# SIM800C.net
KiCad netlist of a schematic drawn in Altium Designer
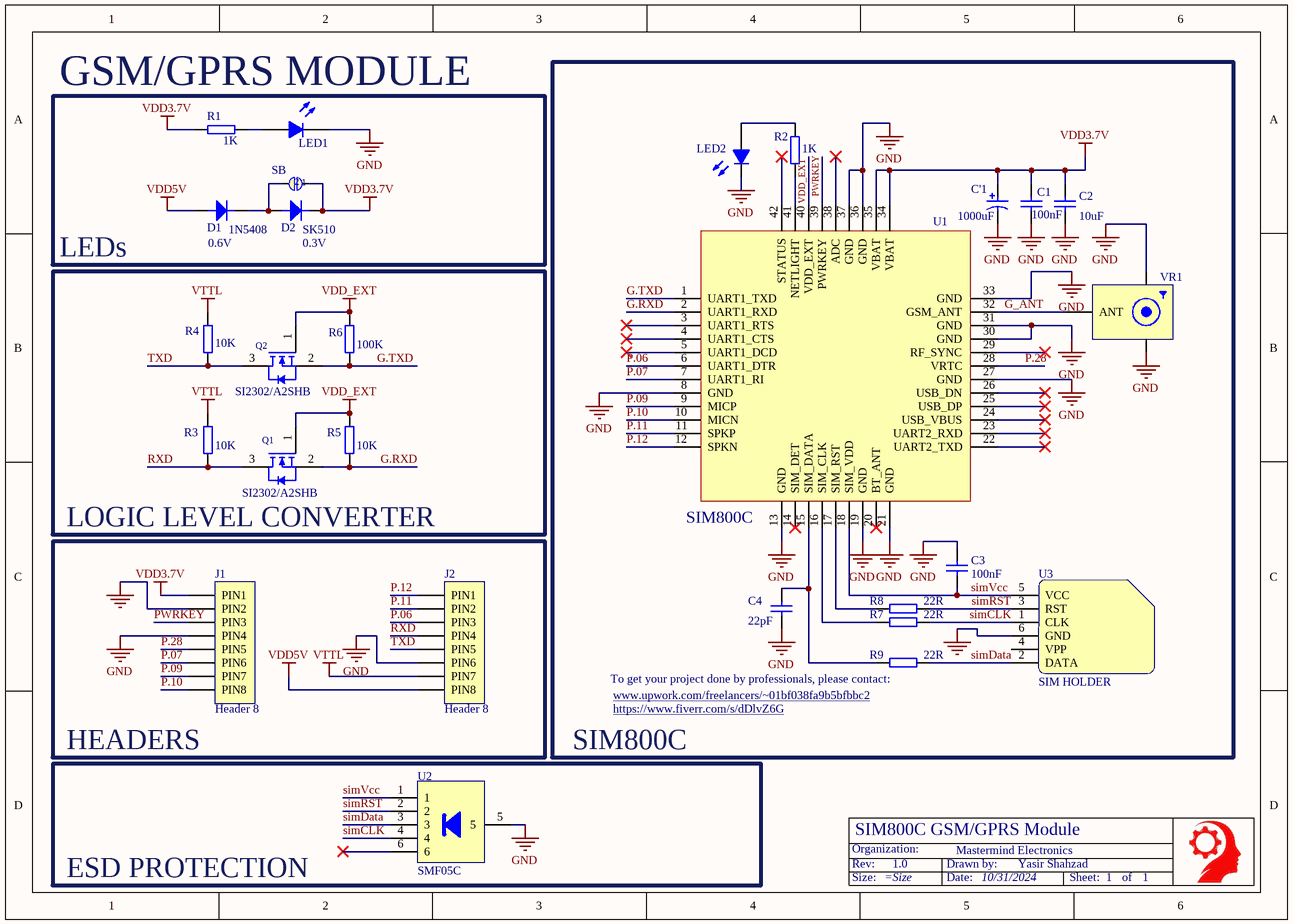
[diagram p0: SIM800C.SchDoc]

(export (version "E")
  (design (tool "Eeschema 10.0.6"))
  (components
    (comp (ref "*")
      (value "TitleBlock")
      (description "Title Block for Schematic Sheets")
      (libsource (lib "mastermind") (part "TitleBlock"))
    )
    (comp (ref "C'1") (value "1000uF") (footprint "D") (libsource (lib "SIM800C") (part "Taltium")))
    (comp (ref "C1")
      (value "10%")
      (footprint "0603C")
      (description "Chip capacitor")
      (libsource (lib "SIM800C") (part "CAP0603_NPOL"))
    )
    (comp (ref "C2")
      (value "10%")
      (footprint "0603C")
      (description "Chip capacitor")
      (libsource (lib "SIM800C") (part "CAP0603_NPOL"))
    )
    (comp (ref "C3")
      (value "10%")
      (footprint "0603C")
      (description "Chip capacitor")
      (libsource (lib "SIM800C") (part "CAP0603_NPOL"))
    )
    (comp (ref "C4")
      (value "10%")
      (footprint "0603C")
      (description "Chip capacitor")
      (libsource (lib "SIM800C") (part "CAP0603_NPOL"))
    )
    (comp (ref "D1")
      (value "DIODE-DO214-AC")
      (footprint "SOD123")
      (libsource (lib "SIM800C") (part "DIODE-DO214-AC"))
    )
    (comp (ref "D2")
      (value "DIODE-DO214-AC")
      (footprint "SOD123")
      (libsource (lib "SIM800C") (part "DIODE-DO214-AC"))
    )
    (comp (ref "J1")
      (value "Header 8")
      (footprint "HDR1X8")
      (description "Header, 8-Pin")
      (fields (field (name "PUBLISHER") "Altium Limited"))
      (libsource (lib "SIM800C") (part "Header 8"))
    )
    (comp (ref "J2")
      (value "Header 8")
      (footprint "HDR1X8")
      (description "Header, 8-Pin")
      (fields (field (name "PUBLISHER") "Altium Limited"))
      (libsource (lib "SIM800C") (part "Header 8"))
    )
    (comp (ref "LED1")
      (value "LED")
      (footprint "0603LED")
      (description "SMD lamp beads")
      (libsource (lib "SIM800C") (part "LEDCHIP-LED0603"))
    )
    (comp (ref "LED2")
      (value "LED")
      (footprint "0603LED")
      (description "SMD lamp beads")
      (libsource (lib "SIM800C") (part "LEDCHIP-LED0603"))
    )
    (comp (ref "Q1")
      (value "A2SHB")
      (footprint "SOT23")
      (description "N Channel Mosfet")
      (libsource (lib "adafruit") (part "BSS138"))
    )
    (comp (ref "Q2")
      (value "A2SHB")
      (footprint "SOT23")
      (description "N Channel Mosfet")
      (libsource (lib "adafruit") (part "BSS138"))
    )
    (comp (ref "R1")
      (value "5%")
      (footprint "0603")
      (description "Chip Resistor")
      (libsource (lib "") (part "RESISTOR_1"))
    )
    (comp (ref "R2")
      (value "5%")
      (footprint "0603")
      (description "Chip Resistor")
      (libsource (lib "") (part "RESISTOR_2"))
    )
    (comp (ref "R3")
      (value "5%")
      (footprint "0603")
      (description "Chip Resistor")
      (libsource (lib "SIM800C") (part "RESISTOR"))
    )
    (comp (ref "R4")
      (value "5%")
      (footprint "0603")
      (description "Chip Resistor")
      (libsource (lib "") (part "RESISTOR_1"))
    )
    (comp (ref "R5")
      (value "5%")
      (footprint "0603")
      (description "Chip Resistor")
      (libsource (lib "") (part "RESISTOR_1"))
    )
    (comp (ref "R6")
      (value "5%")
      (footprint "0603")
      (description "Chip Resistor")
      (libsource (lib "") (part "RESISTOR_1"))
    )
    (comp (ref "R7")
      (value "5%")
      (footprint "0603")
      (description "Chip Resistor")
      (libsource (lib "SIM800C") (part "RESISTOR"))
    )
    (comp (ref "R8")
      (value "5%")
      (footprint "0603")
      (description "Chip Resistor")
      (libsource (lib "SIM800C") (part "RESISTOR"))
    )
    (comp (ref "R9")
      (value "5%")
      (footprint "0603")
      (description "Chip Resistor")
      (libsource (lib "SIM800C") (part "RESISTOR"))
    )
    (comp (ref "SB")
      (value "SB")
      (footprint "Jumper-NO")
      (description "RESISTOR, American symbol")
      (libsource (lib "SIM800C") (part "SB"))
    )
    (comp (ref "U1")
      (value "SIM800C GSM/GPRS Module")
      (footprint "SMD")
      (fields (field (name "DEVICENAME") "SIM800C"))
      (libsource (lib "SIM800C") (part "GSM_SIM800C"))
    )
    (comp (ref "U2") (value "SOT363") (footprint "SOT363") (libsource (lib "SIM800C") (part "SMF05C")))
    (comp (ref "U3") (value "SIM_LOCK") (footprint "SMD-6") (libsource (lib "SIM800C") (part "SIM_LOCK")))
    (comp (ref "VR1")
      (value "SMA Connector   90Â° DIP SMA Connector, 50 Ohm (4UConnector: 07259)")
      (footprint "SMD-3")
      (libsource (lib "SIM800C") (part "PatchAntenna"))
    )
  )
  (nets
    (net (code "1") (name "/G.RXD") (class "Default")
      (node (ref "Q1") (pin "2") (pintype "passive"))
      (node (ref "R5") (pin "1") (pinfunction "1_1") (pintype "passive"))
      (node (ref "U1") (pin "2") (pinfunction "UART1_RXD_2") (pintype "passive"))
    )
    (net (code "2") (name "/G.TXD") (class "Default")
      (node (ref "Q2") (pin "2") (pintype "passive"))
      (node (ref "R6") (pin "1") (pinfunction "1_1") (pintype "passive"))
      (node (ref "U1") (pin "1") (pinfunction "UART1_TXD_1") (pintype "passive"))
    )
    (net (code "3") (name "/G_ANT") (class "Default")
      (node (ref "U1") (pin "32") (pinfunction "GSM_ANT_32") (pintype "passive"))
      (node (ref "VR1") (pin "3") (pinfunction "ANT_3") (pintype "passive"))
    )
    (net (code "4") (name "/P.06") (class "Default")
      (node (ref "J2") (pin "3") (pinfunction "PIN3_3") (pintype "passive"))
      (node (ref "U1") (pin "6") (pinfunction "UART1_DTR_6") (pintype "passive"))
    )
    (net (code "5") (name "/P.07") (class "Default")
      (node (ref "J1") (pin "6") (pinfunction "PIN6_6") (pintype "passive"))
      (node (ref "U1") (pin "7") (pinfunction "UART1_RI_7") (pintype "passive"))
    )
    (net (code "6") (name "/P.09") (class "Default")
      (node (ref "J1") (pin "7") (pinfunction "PIN7_7") (pintype "passive"))
      (node (ref "U1") (pin "9") (pinfunction "MICP_9") (pintype "passive"))
    )
    (net (code "7") (name "/P.10") (class "Default")
      (node (ref "J1") (pin "8") (pinfunction "PIN8_8") (pintype "passive"))
      (node (ref "U1") (pin "10") (pinfunction "MICN_10") (pintype "passive"))
    )
    (net (code "8") (name "/P.11") (class "Default")
      (node (ref "J2") (pin "2") (pinfunction "PIN2_2") (pintype "passive"))
      (node (ref "U1") (pin "11") (pinfunction "SPKP_11") (pintype "passive"))
    )
    (net (code "9") (name "/P.12") (class "Default")
      (node (ref "J2") (pin "1") (pinfunction "PIN1_1") (pintype "passive"))
      (node (ref "U1") (pin "12") (pinfunction "SPKN_12") (pintype "power_in"))
    )
    (net (code "10") (name "/P.28") (class "Default")
      (node (ref "J1") (pin "5") (pinfunction "PIN5_5") (pintype "passive"))
      (node (ref "U1") (pin "28") (pinfunction "VRTC_28") (pintype "passive"))
    )
    (net (code "11") (name "/PWRKEY") (class "Default")
      (node (ref "J1") (pin "3") (pinfunction "PIN3_3") (pintype "passive"))
      (node (ref "U1") (pin "39") (pinfunction "PWRKEY_39") (pintype "power_in"))
    )
    (net (code "12") (name "/RXD") (class "Default")
      (node (ref "J2") (pin "4") (pinfunction "PIN4_4") (pintype "passive"))
      (node (ref "Q1") (pin "3") (pintype "passive"))
      (node (ref "R3") (pin "2") (pinfunction "2_2") (pintype "passive"))
    )
    (net (code "13") (name "/TXD") (class "Default")
      (node (ref "J2") (pin "5") (pinfunction "PIN5_5") (pintype "passive"))
      (node (ref "Q2") (pin "3") (pintype "passive"))
      (node (ref "R4") (pin "1") (pinfunction "1_1") (pintype "passive"))
    )
    (net (code "14") (name "/simCLK") (class "Default")
      (node (ref "R7") (pin "1") (pinfunction "1_1") (pintype "passive"))
      (node (ref "U2") (pin "4") (pinfunction "4_4") (pintype "passive"))
      (node (ref "U3") (pin "1") (pinfunction "CLK_1") (pintype "passive"))
    )
    (net (code "15") (name "/simData") (class "Default")
      (node (ref "R9") (pin "1") (pinfunction "1_1") (pintype "passive"))
      (node (ref "U2") (pin "3") (pinfunction "3_3") (pintype "passive"))
      (node (ref "U3") (pin "2") (pinfunction "DATA_2") (pintype "passive"))
    )
    (net (code "16") (name "/simRST") (class "Default")
      (node (ref "R8") (pin "1") (pinfunction "1_1") (pintype "passive"))
      (node (ref "U2") (pin "2") (pinfunction "2_2") (pintype "passive"))
      (node (ref "U3") (pin "3") (pinfunction "RST_3") (pintype "passive"))
    )
    (net (code "17") (name "/simVcc") (class "Default")
      (node (ref "C3") (pin "2") (pinfunction "2_2") (pintype "passive"))
      (node (ref "U1") (pin "18") (pinfunction "SIM_VDD_18") (pintype "passive"))
      (node (ref "U2") (pin "1") (pinfunction "1_1") (pintype "passive"))
      (node (ref "U3") (pin "5") (pinfunction "VCC_5") (pintype "passive"))
    )
    (net (code "18") (name "GND") (class "Default")
      (node (ref "C'1") (pin "2") (pinfunction "2_2") (pintype "passive"))
      (node (ref "C1") (pin "2") (pinfunction "2_2") (pintype "passive"))
      (node (ref "C2") (pin "2") (pinfunction "2_2") (pintype "passive"))
      (node (ref "C3") (pin "1") (pinfunction "1_1") (pintype "passive"))
      (node (ref "C4") (pin "2") (pinfunction "2_2") (pintype "passive"))
      (node (ref "J1") (pin "2") (pinfunction "PIN2_2") (pintype "passive"))
      (node (ref "J1") (pin "4") (pinfunction "PIN4_4") (pintype "passive"))
      (node (ref "J2") (pin "6") (pinfunction "PIN6_6") (pintype "passive"))
      (node (ref "LED1") (pin "2") (pinfunction "K_2") (pintype "passive"))
      (node (ref "LED2") (pin "2") (pinfunction "K_2") (pintype "passive"))
      (node (ref "U1") (pin "13") (pinfunction "GND_13") (pintype "power_in"))
      (node (ref "U1") (pin "19") (pinfunction "GND_19") (pintype "passive"))
      (node (ref "U1") (pin "21") (pinfunction "GND_21") (pintype "passive"))
      (node (ref "U1") (pin "27") (pinfunction "GND_27") (pintype "passive"))
      (node (ref "U1") (pin "30") (pinfunction "GND_30") (pintype "passive"))
      (node (ref "U1") (pin "31") (pinfunction "GND_31") (pintype "passive"))
      (node (ref "U1") (pin "33") (pinfunction "GND_33") (pintype "power_in"))
      (node (ref "U1") (pin "36") (pinfunction "GND_36") (pintype "power_in"))
      (node (ref "U1") (pin "37") (pinfunction "GND_37") (pintype "power_in"))
      (node (ref "U1") (pin "8") (pinfunction "GND_8") (pintype "passive"))
      (node (ref "U2") (pin "5") (pinfunction "5_5") (pintype "passive"))
      (node (ref "U3") (pin "6") (pinfunction "GND_6") (pintype "passive"))
      (node (ref "VR1") (pin "1") (pinfunction "GND3_1") (pintype "power_in"))
      (node (ref "VR1") (pin "2") (pinfunction "GND1_2") (pintype "power_in"))
    )
    (net (code "19") (name "Net-(D1-C)") (class "Default")
      (node (ref "D1") (pin "2") (pinfunction "C_2") (pintype "passive"))
      (node (ref "D2") (pin "1") (pinfunction "A_1") (pintype "passive"))
      (node (ref "SB") (pin "2") (pinfunction "2_2") (pintype "passive"))
    )
    (net (code "20") (name "Net-(LED1-A)") (class "Default")
      (node (ref "LED1") (pin "1") (pinfunction "A_1") (pintype "passive"))
      (node (ref "R1") (pin "2") (pinfunction "2_2") (pintype "passive"))
    )
    (net (code "21") (name "Net-(LED2-A)") (class "Default")
      (node (ref "LED2") (pin "1") (pinfunction "A_1") (pintype "passive"))
      (node (ref "R2") (pin "2") (pinfunction "2_2") (pintype "passive"))
    )
    (net (code "22") (name "Net-(U1-NETLIGHT)") (class "Default")
      (node (ref "R2") (pin "1") (pinfunction "1_1") (pintype "passive"))
      (node (ref "U1") (pin "41") (pinfunction "NETLIGHT_41") (pintype "power_in"))
    )
    (net (code "23") (name "Net-(U1-SIM_CLK)") (class "Default")
      (node (ref "R7") (pin "2") (pinfunction "2_2") (pintype "passive"))
      (node (ref "U1") (pin "16") (pinfunction "SIM_CLK_16") (pintype "passive"))
    )
    (net (code "24") (name "Net-(U1-SIM_DATA)") (class "Default")
      (node (ref "C4") (pin "1") (pinfunction "1_1") (pintype "passive"))
      (node (ref "R9") (pin "2") (pinfunction "2_2") (pintype "passive"))
      (node (ref "U1") (pin "15") (pinfunction "SIM_DATA_15") (pintype "passive"))
    )
    (net (code "25") (name "Net-(U1-SIM_RST)") (class "Default")
      (node (ref "R8") (pin "2") (pinfunction "2_2") (pintype "passive"))
      (node (ref "U1") (pin "17") (pinfunction "SIM_RST_17") (pintype "passive"))
    )
    (net (code "26") (name "VDD3.7V") (class "Default")
      (node (ref "C'1") (pin "1") (pinfunction "1_1") (pintype "passive"))
      (node (ref "C1") (pin "1") (pinfunction "1_1") (pintype "passive"))
      (node (ref "C2") (pin "1") (pinfunction "1_1") (pintype "passive"))
      (node (ref "D2") (pin "2") (pinfunction "C_2") (pintype "passive"))
      (node (ref "J1") (pin "1") (pinfunction "PIN1_1") (pintype "passive"))
      (node (ref "R1") (pin "1") (pinfunction "1_1") (pintype "passive"))
      (node (ref "SB") (pin "1") (pinfunction "1_1") (pintype "passive"))
      (node (ref "U1") (pin "34") (pinfunction "VBAT_34") (pintype "passive"))
      (node (ref "U1") (pin "35") (pinfunction "VBAT_35") (pintype "passive"))
    )
    (net (code "27") (name "VDD5V") (class "Default")
      (node (ref "D1") (pin "1") (pinfunction "A_1") (pintype "passive"))
      (node (ref "J2") (pin "8") (pinfunction "PIN8_8") (pintype "passive"))
    )
    (net (code "28") (name "VDD_EXT") (class "Default")
      (node (ref "Q1") (pin "1") (pintype "passive"))
      (node (ref "Q2") (pin "1") (pintype "passive"))
      (node (ref "R5") (pin "2") (pinfunction "2_2") (pintype "passive"))
      (node (ref "R6") (pin "2") (pinfunction "2_2") (pintype "passive"))
      (node (ref "U1") (pin "40") (pinfunction "VDD_EXT_40") (pintype "power_in"))
    )
    (net (code "29") (name "VTTL") (class "Default")
      (node (ref "J2") (pin "7") (pinfunction "PIN7_7") (pintype "passive"))
      (node (ref "R3") (pin "1") (pinfunction "1_1") (pintype "passive"))
      (node (ref "R4") (pin "2") (pinfunction "2_2") (pintype "passive"))
    )
    (net (code "30") (name "unconnected-(U1-ADC-Pad38)") (class "Default")
      (node (ref "U1") (pin "38") (pinfunction "ADC_38") (pintype "power_in+no_connect"))
    )
    (net (code "31") (name "unconnected-(U1-BT_ANT-Pad20)") (class "Default")
      (node (ref "U1") (pin "20") (pinfunction "BT_ANT_20") (pintype "passive+no_connect"))
    )
    (net (code "32") (name "unconnected-(U1-RF_SYNC-Pad29)") (class "Default")
      (node (ref "U1") (pin "29") (pinfunction "RF_SYNC_29") (pintype "passive+no_connect"))
    )
    (net (code "33") (name "unconnected-(U1-SIM_DET-Pad14)") (class "Default")
      (node (ref "U1") (pin "14") (pinfunction "SIM_DET_14") (pintype "passive+no_connect"))
    )
    (net (code "34") (name "unconnected-(U1-STATUS-Pad42)") (class "Default")
      (node (ref "U1") (pin "42") (pinfunction "STATUS_42") (pintype "passive+no_connect"))
    )
    (net (code "35") (name "unconnected-(U1-UART1_CTS-Pad4)") (class "Default")
      (node (ref "U1") (pin "4") (pinfunction "UART1_CTS_4") (pintype "passive+no_connect"))
    )
    (net (code "36") (name "unconnected-(U1-UART1_DCD-Pad5)") (class "Default")
      (node (ref "U1") (pin "5") (pinfunction "UART1_DCD_5") (pintype "passive+no_connect"))
    )
    (net (code "37") (name "unconnected-(U1-UART1_RTS-Pad3)") (class "Default")
      (node (ref "U1") (pin "3") (pinfunction "UART1_RTS_3") (pintype "passive+no_connect"))
    )
    (net (code "38") (name "unconnected-(U1-UART2_RXD-Pad23)") (class "Default")
      (node (ref "U1") (pin "23") (pinfunction "UART2_RXD_23") (pintype "passive+no_connect"))
    )
    (net (code "39") (name "unconnected-(U1-UART2_TXD-Pad22)") (class "Default")
      (node (ref "U1") (pin "22") (pinfunction "UART2_TXD_22") (pintype "passive+no_connect"))
    )
    (net (code "40") (name "unconnected-(U1-USB_DN-Pad26)") (class "Default")
      (node (ref "U1") (pin "26") (pinfunction "USB_DN_26") (pintype "power_in+no_connect"))
    )
    (net (code "41") (name "unconnected-(U1-USB_DP-Pad25)") (class "Default")
      (node (ref "U1") (pin "25") (pinfunction "USB_DP_25") (pintype "passive+no_connect"))
    )
    (net (code "42") (name "unconnected-(U1-USB_VBUS-Pad24)") (class "Default")
      (node (ref "U1") (pin "24") (pinfunction "USB_VBUS_24") (pintype "passive+no_connect"))
    )
    (net (code "43") (name "unconnected-(U2-Pad6)") (class "Default")
      (node (ref "U2") (pin "6") (pinfunction "6_6") (pintype "passive+no_connect"))
    )
    (net (code "44") (name "unconnected-(U3-VPP-Pad4)") (class "Default")
      (node (ref "U3") (pin "4") (pinfunction "VPP_4") (pintype "passive"))
    )
  )
)
